# ws2812_Sqaure.net
KiCad netlist of a schematic drawn in EAGLE
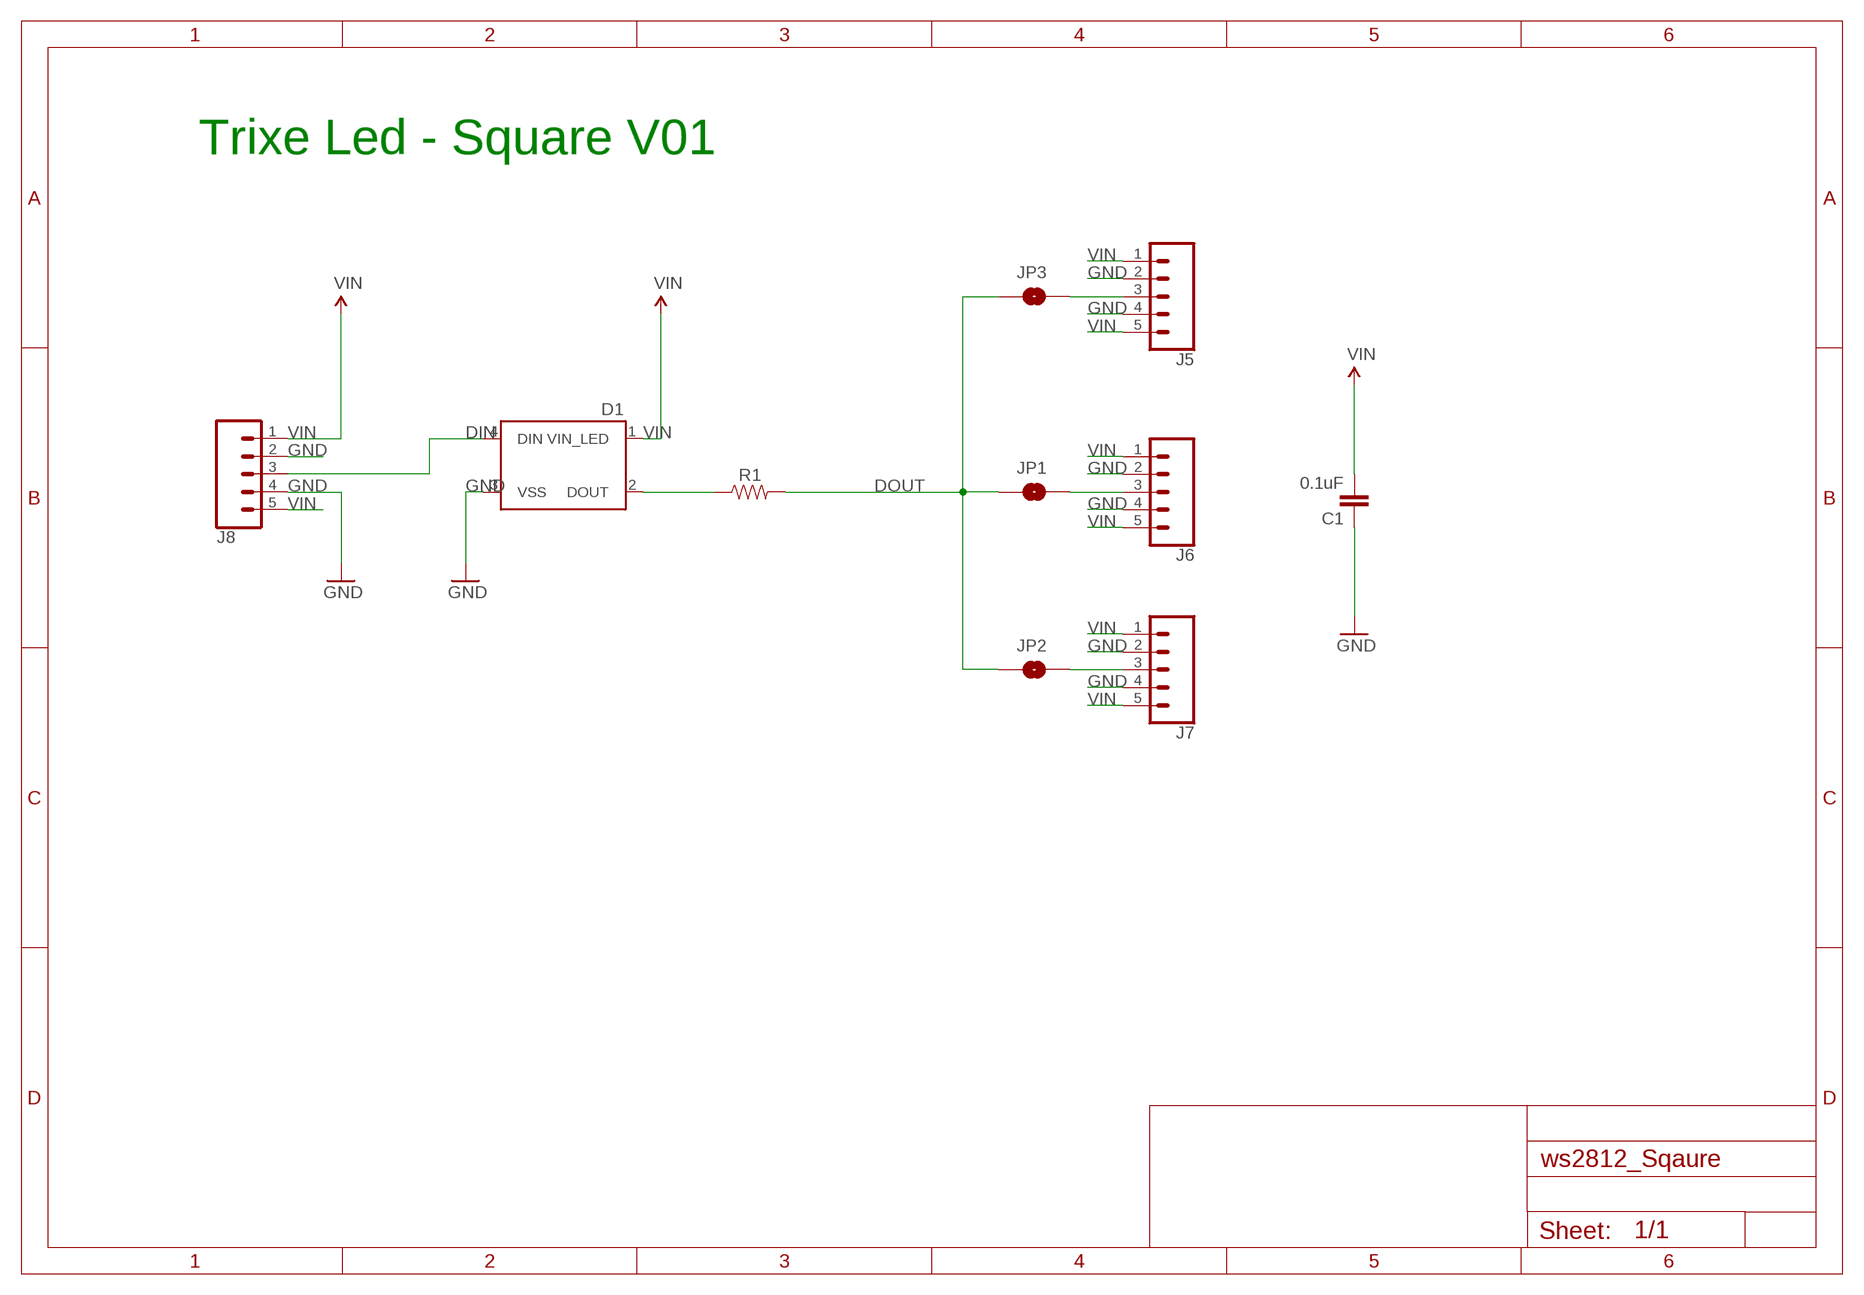
[diagram p0: schematic, sheet 1]

(export (version "E")
  (design (tool "Eeschema 10.0.6"))
  (components
    (comp (ref "C1")
      (value "0.1uF")
      (footprint "eagle-import:0805")
      (libsource (lib "eagle-import") (part "CAP0805"))
    )
    (comp (ref "D1")
      (value "WS2812B")
      (footprint "eagle-import:WS2812B")
      (libsource (lib "eagle-import") (part "WS2812B"))
    )
    (comp (ref "J5")
      (value "CONN_05PTH_LONGPADS")
      (footprint "eagle-import:1X05_LONGPADS")
      (libsource (lib "eagle-import") (part "CONN_05PTH_LONGPADS"))
    )
    (comp (ref "J6")
      (value "CONN_05PTH_LONGPADS")
      (footprint "eagle-import:1X05_LONGPADS")
      (libsource (lib "eagle-import") (part "CONN_05PTH_LONGPADS"))
    )
    (comp (ref "J7")
      (value "CONN_05PTH_LONGPADS")
      (footprint "eagle-import:1X05_LONGPADS")
      (libsource (lib "eagle-import") (part "CONN_05PTH_LONGPADS"))
    )
    (comp (ref "J8")
      (value "CONN_05PTH_LONGPADS")
      (footprint "eagle-import:1X05_LONGPADS")
      (libsource (lib "eagle-import") (part "CONN_05PTH_LONGPADS"))
    )
    (comp (ref "JP1")
      (value "JUMPER-PAD-2-NOYES_SILK")
      (footprint "eagle-import:PAD-JUMPER-2-NO_YES_SILK")
      (libsource (lib "eagle-import") (part "JUMPER-PAD-2-NOYES_SILK"))
    )
    (comp (ref "JP2")
      (value "JUMPER-PAD-2-NOYES_SILK")
      (footprint "eagle-import:PAD-JUMPER-2-NO_YES_SILK")
      (libsource (lib "eagle-import") (part "JUMPER-PAD-2-NOYES_SILK"))
    )
    (comp (ref "JP3")
      (value "JUMPER-PAD-2-NOYES_SILK")
      (footprint "eagle-import:PAD-JUMPER-2-NO_YES_SILK")
      (libsource (lib "eagle-import") (part "JUMPER-PAD-2-NOYES_SILK"))
    )
    (comp (ref "R1")
      (value "RESISTOR0805")
      (footprint "eagle-import:0805")
      (libsource (lib "eagle-import") (part "RESISTOR0805"))
    )
  )
  (nets
    (net (code "1") (name "/DIN") (class "Default")
      (node (ref "D1") (pin "4") (pinfunction "DIN_4") (pintype "input"))
      (node (ref "J8") (pin "3") (pinfunction "3_3") (pintype "passive"))
    )
    (net (code "2") (name "/DOUT") (class "Default")
      (node (ref "JP1") (pin "1") (pinfunction "1_1") (pintype "passive"))
      (node (ref "JP2") (pin "1") (pinfunction "1_1") (pintype "passive"))
      (node (ref "JP3") (pin "1") (pinfunction "1_1") (pintype "passive"))
      (node (ref "R1") (pin "2") (pinfunction "2_2") (pintype "passive"))
    )
    (net (code "3") (name "GND") (class "Default")
      (node (ref "C1") (pin "1") (pinfunction "1_1") (pintype "passive"))
      (node (ref "D1") (pin "3") (pinfunction "VSS_3") (pintype "power_in"))
      (node (ref "J5") (pin "2") (pinfunction "2_2") (pintype "passive"))
      (node (ref "J5") (pin "4") (pinfunction "4_4") (pintype "passive"))
      (node (ref "J6") (pin "2") (pinfunction "2_2") (pintype "passive"))
      (node (ref "J6") (pin "4") (pinfunction "4_4") (pintype "passive"))
      (node (ref "J7") (pin "2") (pinfunction "2_2") (pintype "passive"))
      (node (ref "J7") (pin "4") (pinfunction "4_4") (pintype "passive"))
      (node (ref "J8") (pin "2") (pinfunction "2_2") (pintype "passive"))
      (node (ref "J8") (pin "4") (pinfunction "4_4") (pintype "passive"))
    )
    (net (code "4") (name "Net-(D1-DOUT)") (class "Default")
      (node (ref "D1") (pin "2") (pinfunction "DOUT_2") (pintype "output"))
      (node (ref "R1") (pin "1") (pinfunction "1_1") (pintype "passive"))
    )
    (net (code "5") (name "Net-(J5-Pad3)") (class "Default")
      (node (ref "J5") (pin "3") (pinfunction "3_3") (pintype "passive"))
      (node (ref "JP3") (pin "2") (pinfunction "2_2") (pintype "passive"))
    )
    (net (code "6") (name "Net-(J6-Pad3)") (class "Default")
      (node (ref "J6") (pin "3") (pinfunction "3_3") (pintype "passive"))
      (node (ref "JP1") (pin "2") (pinfunction "2_2") (pintype "passive"))
    )
    (net (code "7") (name "Net-(J7-Pad3)") (class "Default")
      (node (ref "J7") (pin "3") (pinfunction "3_3") (pintype "passive"))
      (node (ref "JP2") (pin "2") (pinfunction "2_2") (pintype "passive"))
    )
    (net (code "8") (name "VIN") (class "Default")
      (node (ref "C1") (pin "2") (pinfunction "2_2") (pintype "passive"))
      (node (ref "D1") (pin "1") (pinfunction "VIN_LED_1") (pintype "power_in"))
      (node (ref "J5") (pin "1") (pinfunction "1_1") (pintype "passive"))
      (node (ref "J5") (pin "5") (pinfunction "5_5") (pintype "passive"))
      (node (ref "J6") (pin "1") (pinfunction "1_1") (pintype "passive"))
      (node (ref "J6") (pin "5") (pinfunction "5_5") (pintype "passive"))
      (node (ref "J7") (pin "1") (pinfunction "1_1") (pintype "passive"))
      (node (ref "J7") (pin "5") (pinfunction "5_5") (pintype "passive"))
      (node (ref "J8") (pin "1") (pinfunction "1_1") (pintype "passive"))
      (node (ref "J8") (pin "5") (pinfunction "5_5") (pintype "passive"))
    )
  )
)
